# THS7002CPWP_Schematic.net
KiCad netlist of a schematic drawn in Altium Designer
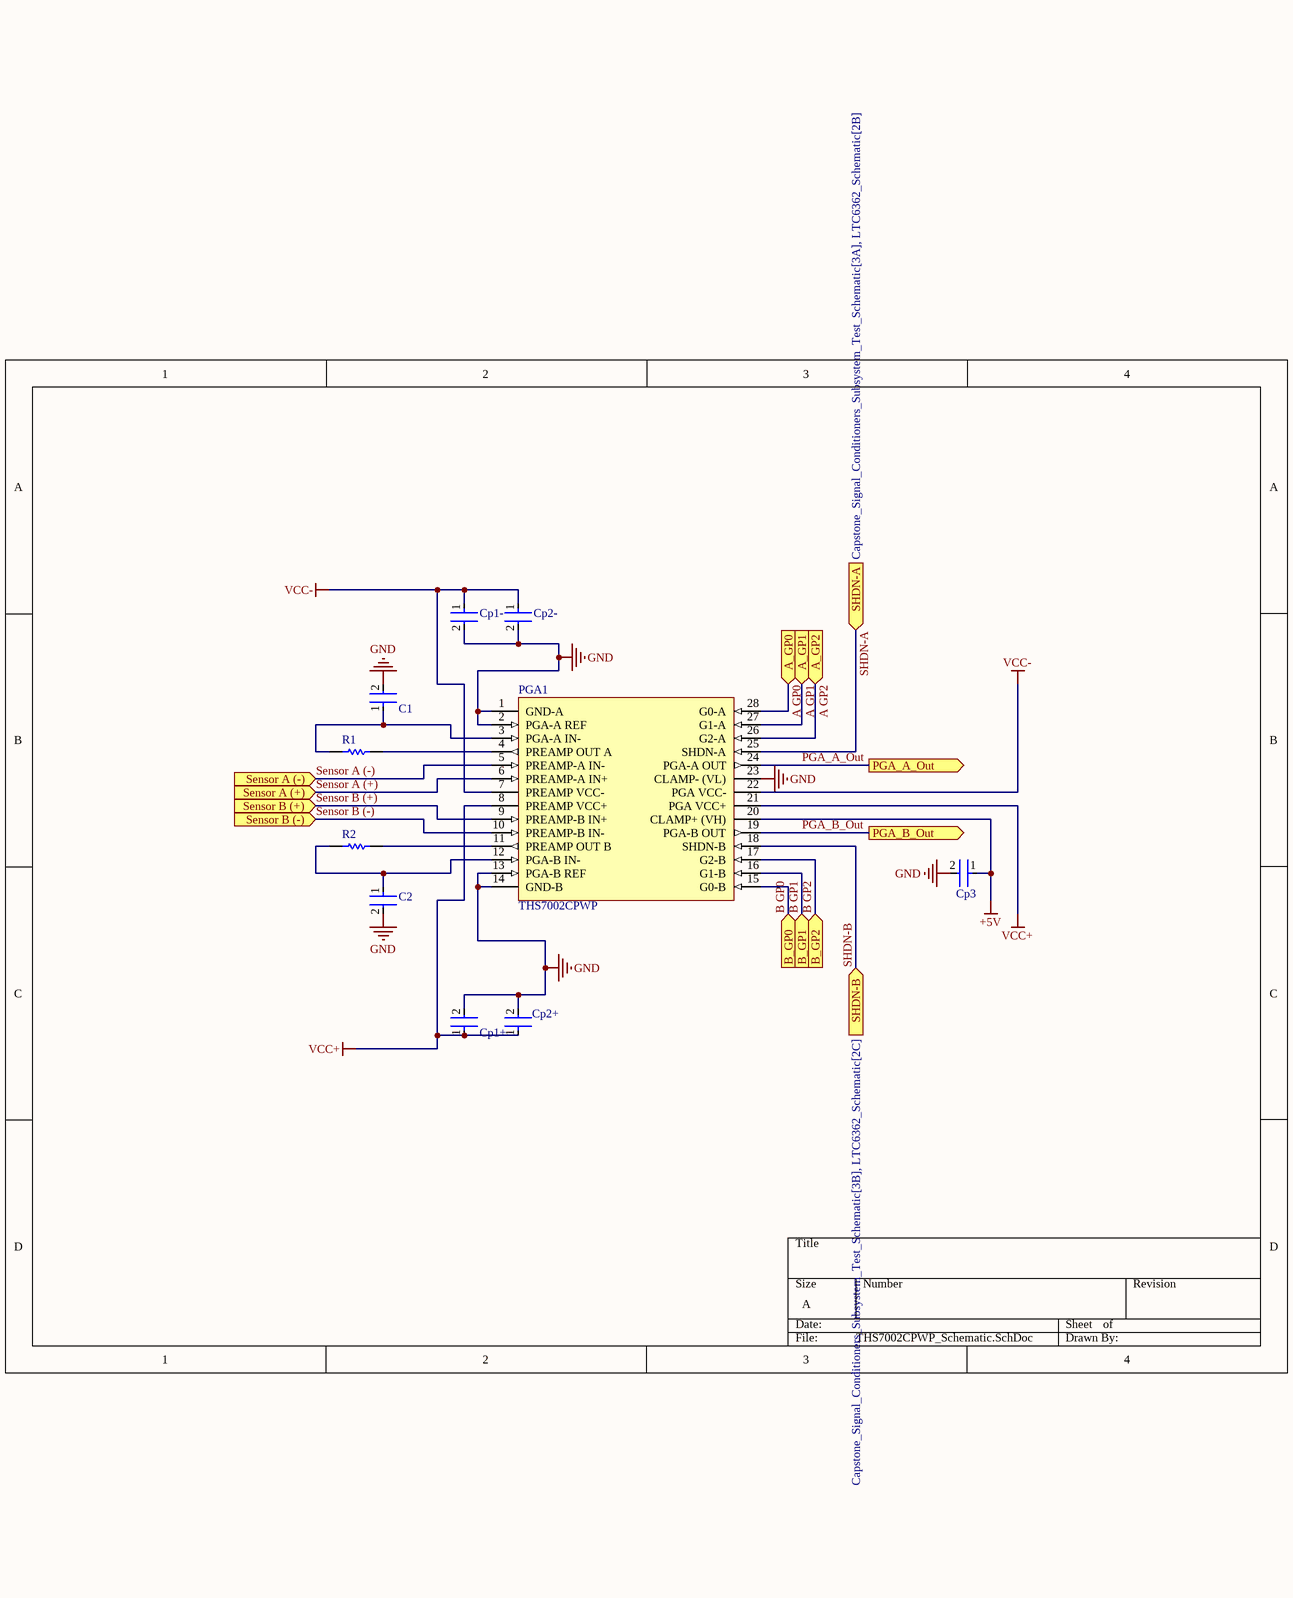
[diagram p0: THS7002CPWP_Schematic.SchDoc]

(export (version "E")
  (design (tool "Eeschema 10.0.6"))
  (components
    (comp (ref "C1")
      (value "GRM3195C1H163JA01D")
      (footprint "FP-GRM319-0_15-IPC_A")
      (description "Chip Multilayer Ceramic Capacitors for General Purpose, 1206, 16000pF, C0G, 30ppm/°C, 5%, 50V")
      (fields (field (name "TOLERANCE") "5%"))
      (libsource (lib "Altium Content Vault") (part "b4654b650e69147ec39a6b967a45e02"))
    )
    (comp (ref "C2")
      (value "GRM3195C1H163JA01D")
      (footprint "FP-GRM319-0_15-IPC_A")
      (description "Chip Multilayer Ceramic Capacitors for General Purpose, 1206, 16000pF, C0G, 30ppm/°C, 5%, 50V")
      (fields (field (name "TOLERANCE") "5%"))
      (libsource (lib "Altium Content Vault") (part "b4654b650e69147ec39a6b967a45e02"))
    )
    (comp (ref "Cp1+")
      (value "CC0603KRX7R7BB104")
      (footprint "FP-CC0603-DA-MFG")
      (description "CAP CER 0.1UF 16V X7R 0603")
      (fields
        (field (name "OCTOPART") "https://octopart.com/cc0603krx7r7bb104-yageo-192941")
        (field (name "TOLERANCE") "0.1")
      )
      (libsource (lib "Altium Content Vault") (part "11868f565c42a9108669ba33697ecf6"))
    )
    (comp (ref "Cp1-")
      (value "CC0603KRX7R7BB104")
      (footprint "FP-CC0603-DA-MFG")
      (description "CAP CER 0.1UF 16V X7R 0603")
      (fields
        (field (name "OCTOPART") "https://octopart.com/cc0603krx7r7bb104-yageo-192941")
        (field (name "TOLERANCE") "0.1")
      )
      (libsource (lib "Altium Content Vault") (part "11868f565c42a9108669ba33697ecf6"))
    )
    (comp (ref "Cp2+")
      (value "C2012JB1A685K060AC")
      (footprint "FP-C2012-060-0_2-IPC_A")
      (description "Multilayer Ceramic Capacitors 6.8μF ±10% 10V JB SMD 0805")
      (fields (field (name "TOLERANCE") "10%"))
      (libsource (lib "Altium Content Vault") (part "b4654b650e69147ec39a6b967a45e02"))
    )
    (comp (ref "Cp2-")
      (value "C2012JB1A685K060AC")
      (footprint "FP-C2012-060-0_2-IPC_A")
      (description "Multilayer Ceramic Capacitors 6.8μF ±10% 10V JB SMD 0805")
      (fields (field (name "TOLERANCE") "10%"))
      (libsource (lib "Altium Content Vault") (part "b4654b650e69147ec39a6b967a45e02"))
    )
    (comp (ref "Cp3")
      (value "C2012JB1A685K060AC")
      (footprint "FP-C2012-060-0_2-IPC_A")
      (description "Multilayer Ceramic Capacitors 6.8μF ±10% 10V JB SMD 0805")
      (fields (field (name "TOLERANCE") "10%"))
      (libsource (lib "Altium Content Vault") (part "b4654b650e69147ec39a6b967a45e02"))
    )
    (comp (ref "PGA1")
      (value "THS7002CPWP")
      (footprint "PWP0028E_M")
      (fields (field (name "MANUFACTURER") "Texas Instruments"))
      (libsource (lib "THS7002CPWP_Symbol") (part "CMP-0988-00132-2"))
    )
    (comp (ref "R1")
      (value "CRCW08050000Z0EA")
      (footprint "RESC2013X50X30LL20T20")
      (fields (field (name "MANUFACTURER") "Vishay Dale"))
      (libsource (lib "Altium Content Vault") (part "RES"))
    )
    (comp (ref "R2")
      (value "CRCW08050000Z0EA")
      (footprint "RESC2013X50X30LL20T20")
      (fields (field (name "MANUFACTURER") "Vishay Dale"))
      (libsource (lib "Altium Content Vault") (part "RES"))
    )
  )
  (nets
    (net (code "1") (name "+5V") (class "Default")
      (node (ref "Cp3") (pin "1") (pinfunction "1_1") (pintype "passive"))
      (node (ref "PGA1") (pin "20") (pinfunction "CLAMP+_(VH)_20") (pintype "power_in"))
    )
    (net (code "2") (name "/A GP0") (class "Default")
      (node (ref "PGA1") (pin "28") (pinfunction "G0-A_28") (pintype "input"))
    )
    (net (code "3") (name "/A GP1") (class "Default")
      (node (ref "PGA1") (pin "27") (pinfunction "G1-A_27") (pintype "input"))
    )
    (net (code "4") (name "/A GP2") (class "Default")
      (node (ref "PGA1") (pin "26") (pinfunction "G2-A_26") (pintype "input"))
    )
    (net (code "5") (name "/B GP0") (class "Default")
      (node (ref "PGA1") (pin "15") (pinfunction "G0-B_15") (pintype "input"))
    )
    (net (code "6") (name "/B GP1") (class "Default")
      (node (ref "PGA1") (pin "16") (pinfunction "G1-B_16") (pintype "input"))
    )
    (net (code "7") (name "/B GP2") (class "Default")
      (node (ref "PGA1") (pin "17") (pinfunction "G2-B_17") (pintype "input"))
    )
    (net (code "8") (name "/PGA_A_Out") (class "Default")
      (node (ref "PGA1") (pin "24") (pinfunction "PGA-A_OUT_24") (pintype "output"))
    )
    (net (code "9") (name "/PGA_B_Out") (class "Default")
      (node (ref "PGA1") (pin "19") (pinfunction "PGA-B_OUT_19") (pintype "output"))
    )
    (net (code "10") (name "/SHDN-A") (class "Default")
      (node (ref "PGA1") (pin "25") (pinfunction "SHDN-A_25") (pintype "input"))
    )
    (net (code "11") (name "/SHDN-B") (class "Default")
      (node (ref "PGA1") (pin "18") (pinfunction "SHDN-B_18") (pintype "input"))
    )
    (net (code "12") (name "/Sensor A (+)") (class "Default")
      (node (ref "PGA1") (pin "6") (pinfunction "PREAMP-A_IN+_6") (pintype "input"))
    )
    (net (code "13") (name "/Sensor A (-)") (class "Default")
      (node (ref "PGA1") (pin "5") (pinfunction "PREAMP-A_IN-_5") (pintype "input"))
    )
    (net (code "14") (name "/Sensor B (+)") (class "Default")
      (node (ref "PGA1") (pin "9") (pinfunction "PREAMP-B_IN+_9") (pintype "input"))
    )
    (net (code "15") (name "/Sensor B (-)") (class "Default")
      (node (ref "PGA1") (pin "10") (pinfunction "PREAMP-B_IN-_10") (pintype "input"))
    )
    (net (code "16") (name "GND") (class "Default")
      (node (ref "C1") (pin "2") (pinfunction "2_2") (pintype "passive"))
      (node (ref "C2") (pin "2") (pinfunction "2_2") (pintype "passive"))
      (node (ref "Cp1+") (pin "2") (pinfunction "2_2") (pintype "passive"))
      (node (ref "Cp1-") (pin "2") (pinfunction "2_2") (pintype "passive"))
      (node (ref "Cp2+") (pin "2") (pinfunction "2_2") (pintype "passive"))
      (node (ref "Cp2-") (pin "2") (pinfunction "2_2") (pintype "passive"))
      (node (ref "Cp3") (pin "2") (pinfunction "2_2") (pintype "passive"))
      (node (ref "PGA1") (pin "1") (pinfunction "GND-A_1") (pintype "power_in"))
      (node (ref "PGA1") (pin "13") (pinfunction "PGA-B_REF_13") (pintype "input"))
      (node (ref "PGA1") (pin "14") (pinfunction "GND-B_14") (pintype "power_in"))
      (node (ref "PGA1") (pin "2") (pinfunction "PGA-A_REF_2") (pintype "input"))
      (node (ref "PGA1") (pin "23") (pinfunction "CLAMP-_(VL)_23") (pintype "power_in"))
    )
    (net (code "17") (name "Net-(PGA1-PGA-A_IN-)") (class "Default")
      (node (ref "C1") (pin "1") (pinfunction "1_1") (pintype "passive"))
      (node (ref "PGA1") (pin "3") (pinfunction "PGA-A_IN-_3") (pintype "input"))
      (node (ref "R1") (pin "1") (pinfunction "1_1") (pintype "passive"))
    )
    (net (code "18") (name "Net-(PGA1-PGA-B_IN-)") (class "Default")
      (node (ref "C2") (pin "1") (pinfunction "1_1") (pintype "passive"))
      (node (ref "PGA1") (pin "12") (pinfunction "PGA-B_IN-_12") (pintype "input"))
      (node (ref "R2") (pin "1") (pinfunction "1_1") (pintype "passive"))
    )
    (net (code "19") (name "Net-(PGA1-PREAMP_OUT_A)") (class "Default")
      (node (ref "PGA1") (pin "4") (pinfunction "PREAMP_OUT_A_4") (pintype "output"))
      (node (ref "R1") (pin "2") (pinfunction "2_2") (pintype "passive"))
    )
    (net (code "20") (name "Net-(PGA1-PREAMP_OUT_B)") (class "Default")
      (node (ref "PGA1") (pin "11") (pinfunction "PREAMP_OUT_B_11") (pintype "output"))
      (node (ref "R2") (pin "2") (pinfunction "2_2") (pintype "passive"))
    )
    (net (code "21") (name "VCC+") (class "Default")
      (node (ref "Cp1+") (pin "1") (pinfunction "1_1") (pintype "passive"))
      (node (ref "Cp2+") (pin "1") (pinfunction "1_1") (pintype "passive"))
      (node (ref "PGA1") (pin "21") (pinfunction "PGA_VCC+_21") (pintype "power_in"))
      (node (ref "PGA1") (pin "8") (pinfunction "PREAMP_VCC+_8") (pintype "power_in"))
    )
    (net (code "22") (name "VCC-") (class "Default")
      (node (ref "Cp1-") (pin "1") (pinfunction "1_1") (pintype "passive"))
      (node (ref "Cp2-") (pin "1") (pinfunction "1_1") (pintype "passive"))
      (node (ref "PGA1") (pin "22") (pinfunction "PGA_VCC-_22") (pintype "power_in"))
      (node (ref "PGA1") (pin "7") (pinfunction "PREAMP_VCC-_7") (pintype "power_in"))
    )
  )
)
